# DB10005_PowerManagement.net
KiCad netlist of a schematic drawn in Altium Designer
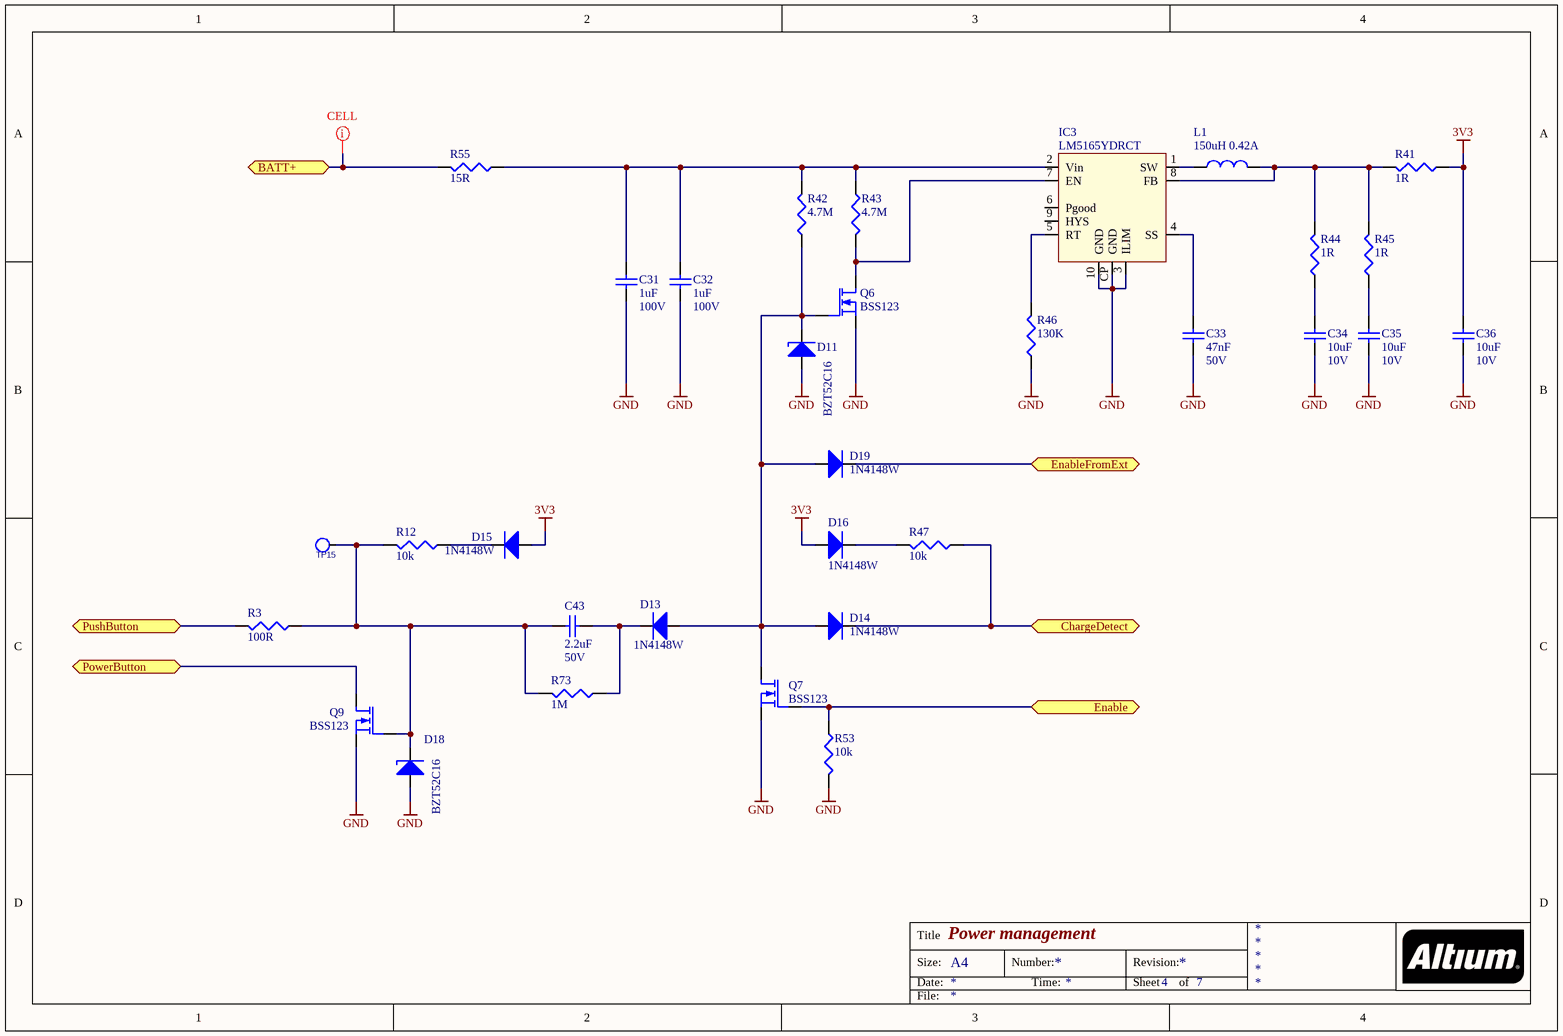
[diagram p0: DB10005_PowerManagement.SchDoc]

(export (version "E")
  (design (tool "Eeschema 10.0.6"))
  (components
    (comp (ref "C31")
      (value "1uF")
      (footprint "C-1206")
      (description "Capacitor, 1uF, 100V, X7R")
      (fields (field (name "VOLTAGE RATING") "100V"))
      (libsource (lib "AR_Capacitors_Ceramic") (part "1uF/1206/CER/100V"))
    )
    (comp (ref "C32")
      (value "1uF")
      (footprint "C-1206")
      (description "Capacitor, 1uF, 100V, X7R")
      (fields (field (name "VOLTAGE RATING") "100V"))
      (libsource (lib "AR_Capacitors_Ceramic") (part "1uF/1206/CER/100V"))
    )
    (comp (ref "C33")
      (value "47nF")
      (footprint "C0603")
      (description "Capacitor, 47nF, 50V, X7R")
      (fields (field (name "VOLTAGE RATING") "50V"))
      (libsource (lib "AR_Capacitors_Ceramic") (part "47nF/0603/CER/50V"))
    )
    (comp (ref "C34")
      (value "10uF")
      (footprint "C-0805")
      (description "Capacitor, 10uF, 10V, X7R")
      (fields (field (name "VOLTAGE RATING") "10V"))
      (libsource (lib "AR_Capacitors_Ceramic") (part "10uF/0805/CER/10V"))
    )
    (comp (ref "C35")
      (value "10uF")
      (footprint "C-0805")
      (description "Capacitor, 10uF, 10V, X7R")
      (fields (field (name "VOLTAGE RATING") "10V"))
      (libsource (lib "AR_Capacitors_Ceramic") (part "10uF/0805/CER/10V"))
    )
    (comp (ref "C36")
      (value "10uF")
      (footprint "C-0805")
      (description "Capacitor, 10uF, 10V, X7R")
      (fields (field (name "VOLTAGE RATING") "10V"))
      (libsource (lib "AR_Capacitors_Ceramic") (part "10uF/0805/CER/10V"))
    )
    (comp (ref "C43")
      (value "2.2uF")
      (footprint "C-0805")
      (description "Capacitor, 2.2uF, 50V,  X7R")
      (fields (field (name "VOLTAGE RATING") "50V"))
      (libsource (lib "AR_Capacitors_Ceramic") (part "2.2uF/0805/CER/50V"))
    )
    (comp (ref "D11")
      (value "BZT52C16")
      (footprint "SOD123")
      (description "Diode Zener, Vz: 16V, If: 0.1A, Vf: 0.9V")
      (libsource (lib "AR_Diodes") (part "BZT52C16"))
    )
    (comp (ref "D13")
      (value "1N4148W")
      (footprint "SOD123")
      (description "Diode, Vrrm: 100V, If: 0.15A, Vf: 1V")
      (libsource (lib "AR_Diodes") (part "MMSD4148T1G"))
    )
    (comp (ref "D14")
      (value "1N4148W")
      (footprint "SOD123")
      (description "Diode, Vrrm: 100V, If: 0.15A, Vf: 1V")
      (libsource (lib "AR_Diodes") (part "MMSD4148T1G"))
    )
    (comp (ref "D15")
      (value "1N4148W")
      (footprint "SOD123")
      (description "Diode, Vrrm: 100V, If: 0.15A, Vf: 1V")
      (libsource (lib "AR_Diodes") (part "MMSD4148T1G"))
    )
    (comp (ref "D16")
      (value "1N4148W")
      (footprint "SOD123")
      (description "Diode, Vrrm: 100V, If: 0.15A, Vf: 1V")
      (libsource (lib "AR_Diodes") (part "MMSD4148T1G"))
    )
    (comp (ref "D18")
      (value "BZT52C16")
      (footprint "SOD123")
      (description "Diode Zener, Vz: 16V, If: 0.1A, Vf: 0.9V")
      (libsource (lib "AR_Diodes") (part "BZT52C16"))
    )
    (comp (ref "D19")
      (value "1N4148W")
      (footprint "SOD123")
      (description "Diode, Vrrm: 100V, If: 0.15A, Vf: 1V")
      (libsource (lib "AR_Diodes") (part "MMSD4148T1G"))
    )
    (comp (ref "IC3")
      (value "LM5165YDRCT")
      (footprint "PWSON10")
      (description "Buck Vreg 150mA 3V3 out 5-65Vin")
      (libsource (lib "AR_Vreg") (part "LM5165Y"))
    )
    (comp (ref "L1")
      (value "150uH 0.42A")
      (footprint "WE-TPC 4828, MH")
      (description "150UH, 30%, 0.42A")
      (libsource (lib "AR_Inductors") (part "744043151"))
    )
    (comp (ref "Q6")
      (value "BSS123")
      (footprint "SOT-23")
      (description "Mosfet, N-channel, Vds:100V, Id:0.15A, Vgs-th:2.8V, Rds-on:3.5ohm")
      (libsource (lib "AR_Mosfets") (part "BSS123"))
    )
    (comp (ref "Q7")
      (value "BSS123")
      (footprint "SOT-23")
      (description "Mosfet, N-channel, Vds:100V, Id:0.15A, Vgs-th:2.8V, Rds-on:3.5ohm")
      (libsource (lib "AR_Mosfets") (part "BSS123"))
    )
    (comp (ref "Q9")
      (value "BSS123")
      (footprint "SOT-23")
      (description "Mosfet, N-channel, Vds:100V, Id:0.15A, Vgs-th:2.8V, Rds-on:3.5ohm")
      (libsource (lib "AR_Mosfets") (part "BSS123"))
    )
    (comp (ref "R3")
      (value "100R")
      (footprint "0805")
      (description "Resistor, 100R, 1%, 0.25W, 150V, 100PPM, 0805")
      (libsource (lib "AR_Resistors_SMD") (part "100/0805/0250W/150V"))
    )
    (comp (ref "R12")
      (value "10k")
      (footprint "0402")
      (description "Resistor, 10k, 0.1%, 0.0625W, 50V, 100PPM, 0402")
      (libsource (lib "AR_Resistors_SMD") (part "10k/0402/0063W/50V"))
    )
    (comp (ref "R41")
      (value "1R")
      (footprint "0805")
      (description "Resistor, 1R, 1%, 0.25W, 150V, 200PPM, 0805")
      (libsource (lib "AR_Resistors_SMD") (part "1/0805/0250W/150V"))
    )
    (comp (ref "R42")
      (value "4.7M")
      (footprint "0805")
      (description "Resistor, 4.7M, 1%, 0.25W, 150V, 100PPM, 0805")
      (libsource (lib "AR_Resistors_SMD") (part "4.7M/0805/0250W/150V"))
    )
    (comp (ref "R43")
      (value "4.7M")
      (footprint "0805")
      (description "Resistor, 4.7M, 1%, 0.25W, 150V, 100PPM, 0805")
      (libsource (lib "AR_Resistors_SMD") (part "4.7M/0805/0250W/150V"))
    )
    (comp (ref "R44")
      (value "1R")
      (footprint "0805")
      (description "Resistor, 1R, 1%, 0.25W, 150V, 200PPM, 0805")
      (libsource (lib "AR_Resistors_SMD") (part "1/0805/0250W/150V"))
    )
    (comp (ref "R45")
      (value "1R")
      (footprint "0805")
      (description "Resistor, 1R, 1%, 0.25W, 150V, 200PPM, 0805")
      (libsource (lib "AR_Resistors_SMD") (part "1/0805/0250W/150V"))
    )
    (comp (ref "R46")
      (value "130K")
      (footprint "0603")
      (description "Resistor, 130K, 1%, 0.063W, 50V, 100PPM, 0603")
      (libsource (lib "AR_Resistors_SMD") (part "130K/0603/0063W/50V"))
    )
    (comp (ref "R47")
      (value "10k")
      (footprint "0402")
      (description "Resistor, 10k, 0.1%, 0.0625W, 50V, 100PPM, 0402")
      (libsource (lib "AR_Resistors_SMD") (part "10k/0402/0063W/50V"))
    )
    (comp (ref "R53")
      (value "10k")
      (footprint "0402")
      (description "Resistor, 10k, 0.1%, 0.0625W, 50V, 100PPM, 0402")
      (libsource (lib "AR_Resistors_SMD") (part "10k/0402/0063W/50V"))
    )
    (comp (ref "R55")
      (value "15R")
      (footprint "0805")
      (description "Resistor, 15R, 0.1%, 0.125W, 150V, 15PPM, 0805")
      (libsource (lib "AR_Resistors_SMD") (part "15/0805/0125W/150V"))
    )
    (comp (ref "R73")
      (value "1M")
      (footprint "0402")
      (description "Resistor, 1M, 0.1%, 0.0625W, 50V, 100PPM, 0402")
      (libsource (lib "AR_Resistors_SMD") (part "1M/0402/0063W/50V"))
    )
    (comp (ref "TP15")
      (value "1.3TP")
      (footprint "TP2-1.3MM")
      (description "1.3mm")
      (libsource (lib "AR_Misc") (part "TESTPT4"))
    )
  )
  (nets
    (net (code "1") (name "/BATT+") (class "Default")
      (node (ref "R55") (pin "2") (pinfunction "2_2") (pintype "passive"))
    )
    (net (code "2") (name "/ChargeDetect") (class "Default")
      (node (ref "D14") (pin "2") (pinfunction "K_2") (pintype "passive"))
      (node (ref "R47") (pin "1") (pinfunction "1_1") (pintype "passive"))
    )
    (net (code "3") (name "/Enable") (class "Default")
      (node (ref "Q7") (pin "G") (pinfunction "G_G") (pintype "passive"))
      (node (ref "R53") (pin "1") (pinfunction "1_1") (pintype "passive"))
    )
    (net (code "4") (name "/EnableFromExt") (class "Default")
      (node (ref "D19") (pin "2") (pinfunction "K_2") (pintype "passive"))
    )
    (net (code "5") (name "/PowerButton") (class "Default")
      (node (ref "Q9") (pin "D") (pinfunction "D_D") (pintype "passive"))
    )
    (net (code "6") (name "/PushButton") (class "Default")
      (node (ref "R3") (pin "2") (pinfunction "2_2") (pintype "passive"))
    )
    (net (code "7") (name "3V3") (class "Default")
      (node (ref "C36") (pin "2") (pinfunction "2_2") (pintype "passive"))
      (node (ref "D15") (pin "1") (pinfunction "A_1") (pintype "passive"))
      (node (ref "D16") (pin "1") (pinfunction "A_1") (pintype "passive"))
      (node (ref "R41") (pin "1") (pinfunction "1_1") (pintype "passive"))
    )
    (net (code "8") (name "GND") (class "Default")
      (node (ref "C31") (pin "1") (pinfunction "1_1") (pintype "passive"))
      (node (ref "C32") (pin "1") (pinfunction "1_1") (pintype "passive"))
      (node (ref "C33") (pin "1") (pinfunction "1_1") (pintype "passive"))
      (node (ref "C34") (pin "1") (pinfunction "1_1") (pintype "passive"))
      (node (ref "C35") (pin "1") (pinfunction "1_1") (pintype "passive"))
      (node (ref "C36") (pin "1") (pinfunction "1_1") (pintype "passive"))
      (node (ref "D11") (pin "1") (pinfunction "A_1") (pintype "passive"))
      (node (ref "D18") (pin "1") (pinfunction "A_1") (pintype "passive"))
      (node (ref "IC3") (pin "10") (pinfunction "GND_10") (pintype "passive"))
      (node (ref "IC3") (pin "3") (pinfunction "ILIM_3") (pintype "passive"))
      (node (ref "IC3") (pin "CP") (pinfunction "GND_CP") (pintype "passive"))
      (node (ref "Q6") (pin "S") (pinfunction "S_S") (pintype "passive"))
      (node (ref "Q7") (pin "S") (pinfunction "S_S") (pintype "passive"))
      (node (ref "Q9") (pin "S") (pinfunction "S_S") (pintype "passive"))
      (node (ref "R46") (pin "1") (pinfunction "1_1") (pintype "passive"))
      (node (ref "R53") (pin "2") (pinfunction "2_2") (pintype "passive"))
    )
    (net (code "9") (name "Net-(C34-Pad2)") (class "Default")
      (node (ref "C34") (pin "2") (pinfunction "2_2") (pintype "passive"))
      (node (ref "R44") (pin "1") (pinfunction "1_1") (pintype "passive"))
    )
    (net (code "10") (name "Net-(C35-Pad2)") (class "Default")
      (node (ref "C35") (pin "2") (pinfunction "2_2") (pintype "passive"))
      (node (ref "R45") (pin "1") (pinfunction "1_1") (pintype "passive"))
    )
    (net (code "11") (name "Net-(D11-K)") (class "Default")
      (node (ref "D11") (pin "2") (pinfunction "K_2") (pintype "passive"))
      (node (ref "D13") (pin "1") (pinfunction "A_1") (pintype "passive"))
      (node (ref "D14") (pin "1") (pinfunction "A_1") (pintype "passive"))
      (node (ref "D19") (pin "1") (pinfunction "A_1") (pintype "passive"))
      (node (ref "Q6") (pin "G") (pinfunction "G_G") (pintype "passive"))
      (node (ref "Q7") (pin "D") (pinfunction "D_D") (pintype "passive"))
      (node (ref "R42") (pin "1") (pinfunction "1_1") (pintype "passive"))
    )
    (net (code "12") (name "Net-(D13-K)") (class "Default")
      (node (ref "C43") (pin "2") (pinfunction "2_2") (pintype "passive"))
      (node (ref "D13") (pin "2") (pinfunction "K_2") (pintype "passive"))
      (node (ref "R73") (pin "1") (pinfunction "1_1") (pintype "passive"))
    )
    (net (code "13") (name "Net-(D15-K)") (class "Default")
      (node (ref "D15") (pin "2") (pinfunction "K_2") (pintype "passive"))
      (node (ref "R12") (pin "1") (pinfunction "1_1") (pintype "passive"))
    )
    (net (code "14") (name "Net-(D16-K)") (class "Default")
      (node (ref "D16") (pin "2") (pinfunction "K_2") (pintype "passive"))
      (node (ref "R47") (pin "2") (pinfunction "2_2") (pintype "passive"))
    )
    (net (code "15") (name "Net-(D18-K)") (class "Default")
      (node (ref "C43") (pin "1") (pinfunction "1_1") (pintype "passive"))
      (node (ref "D18") (pin "2") (pinfunction "K_2") (pintype "passive"))
      (node (ref "Q9") (pin "G") (pinfunction "G_G") (pintype "passive"))
      (node (ref "R12") (pin "2") (pinfunction "2_2") (pintype "passive"))
      (node (ref "R3") (pin "1") (pinfunction "1_1") (pintype "passive"))
      (node (ref "R73") (pin "2") (pinfunction "2_2") (pintype "passive"))
      (node (ref "TP15") (pin "1") (pinfunction "TP_1") (pintype "passive"))
    )
    (net (code "16") (name "Net-(IC3-EN)") (class "Default")
      (node (ref "IC3") (pin "7") (pinfunction "EN_7") (pintype "passive"))
      (node (ref "Q6") (pin "D") (pinfunction "D_D") (pintype "passive"))
      (node (ref "R43") (pin "2") (pinfunction "2_2") (pintype "passive"))
    )
    (net (code "17") (name "Net-(IC3-FB)") (class "Default")
      (node (ref "IC3") (pin "8") (pinfunction "FB_8") (pintype "passive"))
      (node (ref "L1") (pin "2") (pinfunction "2_2") (pintype "passive"))
      (node (ref "R41") (pin "2") (pinfunction "2_2") (pintype "passive"))
      (node (ref "R44") (pin "2") (pinfunction "2_2") (pintype "passive"))
      (node (ref "R45") (pin "2") (pinfunction "2_2") (pintype "passive"))
    )
    (net (code "18") (name "Net-(IC3-RT)") (class "Default")
      (node (ref "IC3") (pin "5") (pinfunction "RT_5") (pintype "passive"))
      (node (ref "R46") (pin "2") (pinfunction "2_2") (pintype "passive"))
    )
    (net (code "19") (name "Net-(IC3-SS)") (class "Default")
      (node (ref "C33") (pin "2") (pinfunction "2_2") (pintype "passive"))
      (node (ref "IC3") (pin "4") (pinfunction "SS_4") (pintype "passive"))
    )
    (net (code "20") (name "Net-(IC3-SW)") (class "Default")
      (node (ref "IC3") (pin "1") (pinfunction "SW_1") (pintype "passive"))
      (node (ref "L1") (pin "1") (pinfunction "1_1") (pintype "passive"))
    )
    (net (code "21") (name "Net-(IC3-Vin)") (class "Default")
      (node (ref "C31") (pin "2") (pinfunction "2_2") (pintype "passive"))
      (node (ref "C32") (pin "2") (pinfunction "2_2") (pintype "passive"))
      (node (ref "IC3") (pin "2") (pinfunction "Vin_2") (pintype "passive"))
      (node (ref "R42") (pin "2") (pinfunction "2_2") (pintype "passive"))
      (node (ref "R43") (pin "1") (pinfunction "1_1") (pintype "passive"))
      (node (ref "R55") (pin "1") (pinfunction "1_1") (pintype "passive"))
    )
    (net (code "22") (name "unconnected-(IC3-HYS-Pad9)") (class "Default")
      (node (ref "IC3") (pin "9") (pinfunction "HYS_9") (pintype "passive"))
    )
    (net (code "23") (name "unconnected-(IC3-Pgood-Pad6)") (class "Default")
      (node (ref "IC3") (pin "6") (pinfunction "Pgood_6") (pintype "passive"))
    )
  )
)
